# Schematic_1d_PingPong.net
KiCad netlist of a schematic drawn in EasyEDA
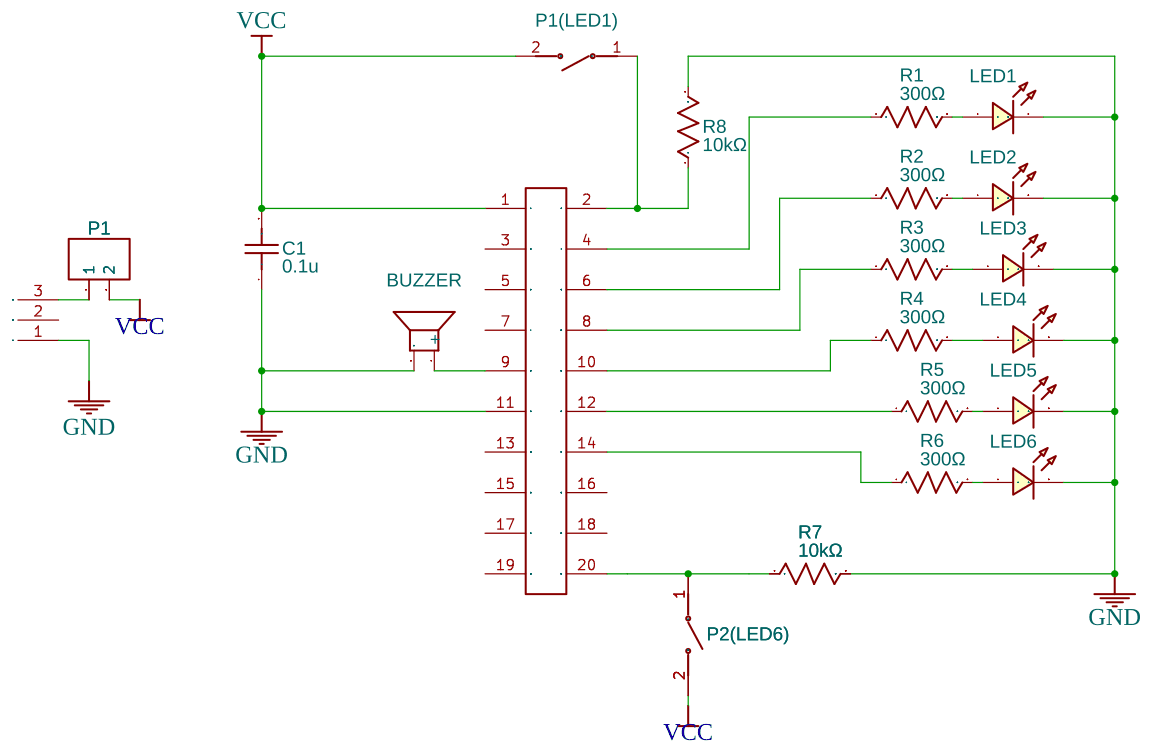
[diagram p0: schematic sheet]

(export (version "E")
  (design (tool "Eeschema 10.0.6"))
  (components
    (comp (ref "BUZZER")
      (value "BUZZER-12X9")
      (fields (field (name "Manufacturer Part") "buzzer-12X9"))
      (libsource (lib "") (part "BUZZER-12X9"))
    )
    (comp (ref "C1") (value "0.1u") (libsource (lib "") (part "C_0603_US")))
    (comp (ref "LED1")
      (value "LED-0603_R")
      (fields
        (field (name "Manufacturer Part") "19-217/R6C-AL1M2VY/3T")
        (field (name "Manufacturer") "EVERLIGHT(台湾亿光)")
      )
      (libsource (lib "") (part "LED-0603_R"))
    )
    (comp (ref "LED2")
      (value "LED-0603_R")
      (fields
        (field (name "Manufacturer Part") "19-217/R6C-AL1M2VY/3T")
        (field (name "Manufacturer") "EVERLIGHT(台湾亿光)")
      )
      (libsource (lib "") (part "LED-0603_R"))
    )
    (comp (ref "LED3")
      (value "LED-0603_R")
      (fields
        (field (name "Manufacturer Part") "19-217/R6C-AL1M2VY/3T")
        (field (name "Manufacturer") "EVERLIGHT(台湾亿光)")
      )
      (libsource (lib "") (part "LED-0603_R"))
    )
    (comp (ref "LED4")
      (value "LED-0603_R")
      (fields
        (field (name "Manufacturer Part") "19-217/R6C-AL1M2VY/3T")
        (field (name "Manufacturer") "EVERLIGHT(台湾亿光)")
      )
      (libsource (lib "") (part "LED-0603_R"))
    )
    (comp (ref "LED5")
      (value "LED-0603_R")
      (fields
        (field (name "Manufacturer Part") "19-217/R6C-AL1M2VY/3T")
        (field (name "Manufacturer") "EVERLIGHT(台湾亿光)")
      )
      (libsource (lib "") (part "LED-0603_R"))
    )
    (comp (ref "LED6")
      (value "LED-0603_R")
      (fields
        (field (name "Manufacturer Part") "19-217/R6C-AL1M2VY/3T")
        (field (name "Manufacturer") "EVERLIGHT(台湾亿光)")
      )
      (libsource (lib "") (part "LED-0603_R"))
    )
    (comp (ref "P1") (value "CONN-TH_2P-P5.00") (libsource (lib "") (part "CONN-TH_2P-P5.00")))
    (comp (ref "P1(LED1)") (value "BUTTON") (libsource (lib "") (part "BUTTON_1")))
    (comp (ref "P2(LED6)") (value "BUTTON") (libsource (lib "") (part "BUTTON")))
    (comp (ref "R1") (value "300Ω") (libsource (lib "") (part "R_0603_US")))
    (comp (ref "R2") (value "300Ω") (libsource (lib "") (part "R_0603_US")))
    (comp (ref "R3") (value "300Ω") (libsource (lib "") (part "R_0603_US")))
    (comp (ref "R4") (value "300Ω") (libsource (lib "") (part "R_0603_US")))
    (comp (ref "R5") (value "300Ω") (libsource (lib "") (part "R_0603_US")))
    (comp (ref "R6") (value "300Ω") (libsource (lib "") (part "R_0603_US")))
    (comp (ref "R7") (value "10kΩ") (libsource (lib "") (part "R_0603_US")))
    (comp (ref "R8") (value "10kΩ") (libsource (lib "") (part "R_0603_US_1")))
    (comp (ref "U1") (value "Tumbler_Large") (libsource (lib "") (part "Tumbler_Large")))
    (comp (ref "X1") (value "PIN_HEADER_2x10") (libsource (lib "") (part "PIN_HEADER_2x10")))
  )
  (nets
    (net (code "1") (name "GND") (class "Default")
      (node (ref "BUZZER") (pin "2") (pinfunction "2_2") (pintype "unspecified"))
      (node (ref "C1") (pin "1") (pinfunction "1_1") (pintype "unspecified"))
      (node (ref "LED1") (pin "2") (pinfunction "2_2") (pintype "unspecified"))
      (node (ref "LED2") (pin "2") (pinfunction "2_2") (pintype "unspecified"))
      (node (ref "LED3") (pin "2") (pinfunction "2_2") (pintype "unspecified"))
      (node (ref "LED4") (pin "2") (pinfunction "2_2") (pintype "unspecified"))
      (node (ref "LED5") (pin "2") (pinfunction "2_2") (pintype "unspecified"))
      (node (ref "LED6") (pin "2") (pinfunction "2_2") (pintype "unspecified"))
      (node (ref "R7") (pin "2") (pinfunction "2_2") (pintype "unspecified"))
      (node (ref "R8") (pin "2") (pinfunction "2_2") (pintype "unspecified"))
      (node (ref "U1") (pin "1") (pinfunction "1_1") (pintype "unspecified"))
      (node (ref "X1") (pin "11") (pinfunction "11_11") (pintype "unspecified"))
    )
    (net (code "2") (name "Net-(BUZZER-+)") (class "Default")
      (node (ref "BUZZER") (pin "1") (pinfunction "+_1") (pintype "unspecified"))
      (node (ref "X1") (pin "9") (pinfunction "9_9") (pintype "unspecified"))
    )
    (net (code "3") (name "Net-(LED1-Pad1)") (class "Default")
      (node (ref "LED1") (pin "1") (pinfunction "1_1") (pintype "unspecified"))
      (node (ref "R1") (pin "2") (pinfunction "2_2") (pintype "unspecified"))
    )
    (net (code "4") (name "Net-(LED2-Pad1)") (class "Default")
      (node (ref "LED2") (pin "1") (pinfunction "1_1") (pintype "unspecified"))
      (node (ref "R2") (pin "2") (pinfunction "2_2") (pintype "unspecified"))
    )
    (net (code "5") (name "Net-(LED3-Pad1)") (class "Default")
      (node (ref "LED3") (pin "1") (pinfunction "1_1") (pintype "unspecified"))
      (node (ref "R3") (pin "2") (pinfunction "2_2") (pintype "unspecified"))
    )
    (net (code "6") (name "Net-(LED4-Pad1)") (class "Default")
      (node (ref "LED4") (pin "1") (pinfunction "1_1") (pintype "unspecified"))
      (node (ref "R4") (pin "2") (pinfunction "2_2") (pintype "unspecified"))
    )
    (net (code "7") (name "Net-(LED5-Pad1)") (class "Default")
      (node (ref "LED5") (pin "1") (pinfunction "1_1") (pintype "unspecified"))
      (node (ref "R5") (pin "2") (pinfunction "2_2") (pintype "unspecified"))
    )
    (net (code "8") (name "Net-(LED6-Pad1)") (class "Default")
      (node (ref "LED6") (pin "1") (pinfunction "1_1") (pintype "unspecified"))
      (node (ref "R6") (pin "2") (pinfunction "2_2") (pintype "unspecified"))
    )
    (net (code "9") (name "Net-(P1(LED1)-Pad1)") (class "Default")
      (node (ref "P1(LED1)") (pin "1") (pinfunction "1_1") (pintype "unspecified"))
      (node (ref "R8") (pin "1") (pinfunction "1_1") (pintype "unspecified"))
      (node (ref "X1") (pin "2") (pinfunction "2_2") (pintype "unspecified"))
    )
    (net (code "10") (name "Net-(P1-Pad1)") (class "Default")
      (node (ref "P1") (pin "1") (pinfunction "1_1") (pintype "unspecified"))
      (node (ref "U1") (pin "3") (pinfunction "3_3") (pintype "unspecified"))
    )
    (net (code "11") (name "Net-(P2(LED6)-Pad1)") (class "Default")
      (node (ref "P2(LED6)") (pin "1") (pinfunction "1_1") (pintype "unspecified"))
      (node (ref "R7") (pin "1") (pinfunction "1_1") (pintype "unspecified"))
      (node (ref "X1") (pin "20") (pinfunction "20_20") (pintype "unspecified"))
    )
    (net (code "12") (name "Net-(R1-Pad1)") (class "Default")
      (node (ref "R1") (pin "1") (pinfunction "1_1") (pintype "unspecified"))
      (node (ref "X1") (pin "4") (pinfunction "4_4") (pintype "unspecified"))
    )
    (net (code "13") (name "Net-(R2-Pad1)") (class "Default")
      (node (ref "R2") (pin "1") (pinfunction "1_1") (pintype "unspecified"))
      (node (ref "X1") (pin "6") (pinfunction "6_6") (pintype "unspecified"))
    )
    (net (code "14") (name "Net-(R3-Pad1)") (class "Default")
      (node (ref "R3") (pin "1") (pinfunction "1_1") (pintype "unspecified"))
      (node (ref "X1") (pin "8") (pinfunction "8_8") (pintype "unspecified"))
    )
    (net (code "15") (name "Net-(R4-Pad1)") (class "Default")
      (node (ref "R4") (pin "1") (pinfunction "1_1") (pintype "unspecified"))
      (node (ref "X1") (pin "10") (pinfunction "10_10") (pintype "unspecified"))
    )
    (net (code "16") (name "Net-(R5-Pad1)") (class "Default")
      (node (ref "R5") (pin "1") (pinfunction "1_1") (pintype "unspecified"))
      (node (ref "X1") (pin "12") (pinfunction "12_12") (pintype "unspecified"))
    )
    (net (code "17") (name "Net-(R6-Pad1)") (class "Default")
      (node (ref "R6") (pin "1") (pinfunction "1_1") (pintype "unspecified"))
      (node (ref "X1") (pin "14") (pinfunction "14_14") (pintype "unspecified"))
    )
    (net (code "18") (name "VCC") (class "Default")
      (node (ref "C1") (pin "2") (pinfunction "2_2") (pintype "unspecified"))
      (node (ref "P1") (pin "2") (pinfunction "2_2") (pintype "unspecified"))
      (node (ref "P1(LED1)") (pin "2") (pinfunction "2_2") (pintype "unspecified"))
      (node (ref "P2(LED6)") (pin "2") (pinfunction "2_2") (pintype "unspecified"))
      (node (ref "X1") (pin "1") (pinfunction "1_1") (pintype "unspecified"))
    )
    (net (code "19") (name "unconnected-(U1-Pad2)") (class "Default")
      (node (ref "U1") (pin "2") (pinfunction "2_2") (pintype "unspecified"))
    )
    (net (code "20") (name "unconnected-(X1-Pad3)") (class "Default")
      (node (ref "X1") (pin "3") (pinfunction "3_3") (pintype "unspecified"))
    )
    (net (code "21") (name "unconnected-(X1-Pad5)") (class "Default")
      (node (ref "X1") (pin "5") (pinfunction "5_5") (pintype "unspecified"))
    )
    (net (code "22") (name "unconnected-(X1-Pad7)") (class "Default")
      (node (ref "X1") (pin "7") (pinfunction "7_7") (pintype "unspecified"))
    )
    (net (code "23") (name "unconnected-(X1-Pad13)") (class "Default")
      (node (ref "X1") (pin "13") (pinfunction "13_13") (pintype "unspecified"))
    )
    (net (code "24") (name "unconnected-(X1-Pad15)") (class "Default")
      (node (ref "X1") (pin "15") (pinfunction "15_15") (pintype "unspecified"))
    )
    (net (code "25") (name "unconnected-(X1-Pad16)") (class "Default")
      (node (ref "X1") (pin "16") (pinfunction "16_16") (pintype "unspecified"))
    )
    (net (code "26") (name "unconnected-(X1-Pad17)") (class "Default")
      (node (ref "X1") (pin "17") (pinfunction "17_17") (pintype "unspecified"))
    )
    (net (code "27") (name "unconnected-(X1-Pad18)") (class "Default")
      (node (ref "X1") (pin "18") (pinfunction "18_18") (pintype "unspecified"))
    )
    (net (code "28") (name "unconnected-(X1-Pad19)") (class "Default")
      (node (ref "X1") (pin "19") (pinfunction "19_19") (pintype "unspecified"))
    )
  )
)
